# design.net
KiCad netlist of a schematic drawn in Altium Designer
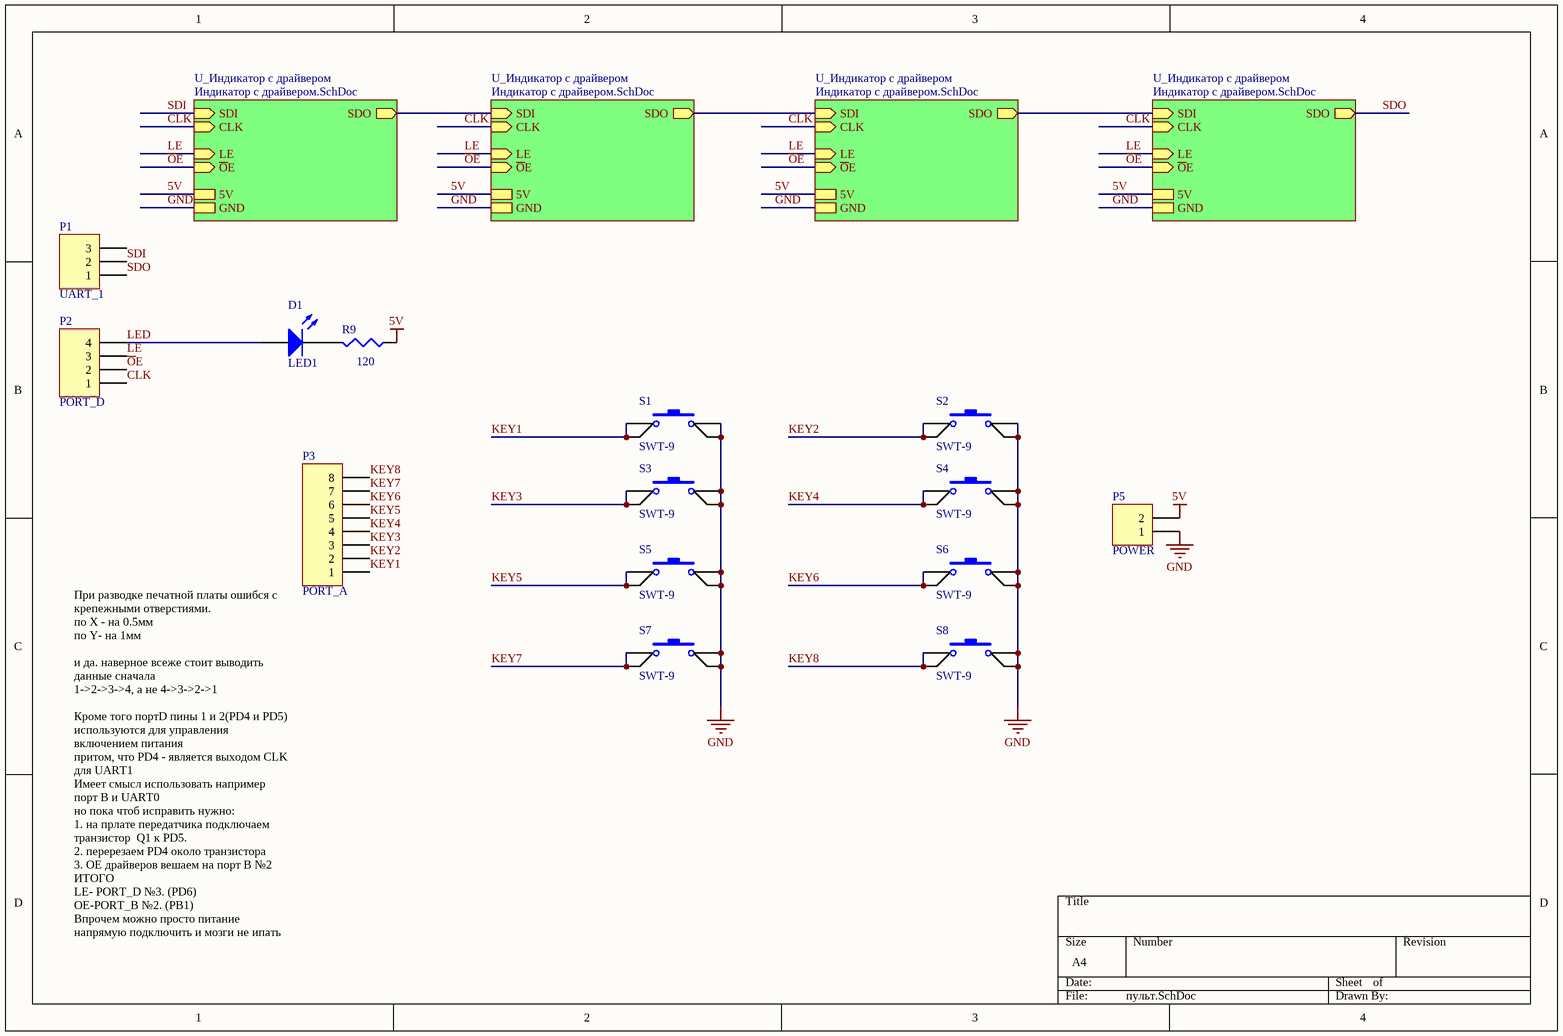
[diagram p0: пульт.SchDoc]

(export (version "E")
  (design (tool "Eeschema 10.0.6"))
  (components
    (comp (ref "D1")
      (value "LED1")
      (footprint "LED-1")
      (description "Typical RED GaAs LED")
      (fields (field (name "PUBLISHER") "Altium Limited"))
      (libsource (lib "Miscellaneous Devices") (part "LED1"))
    )
    (comp (ref "P1")
      (value "UART_1")
      (footprint "HDR1X3H")
      (description "Header, 3-Pin, Right Angle")
      (fields (field (name "PUBLISHER") "Altium Limited"))
      (libsource (lib "Miscellaneous Connectors") (part "Header 3H"))
    )
    (comp (ref "P2")
      (value "PORT_D")
      (footprint "HDR1X4H")
      (description "Header, 4-Pin, Right Angle")
      (fields (field (name "PUBLISHER") "Altium Limited"))
      (libsource (lib "Miscellaneous Connectors") (part "Header 4H"))
    )
    (comp (ref "P3")
      (value "PORT_A")
      (footprint "HDR1X8H")
      (description "Header, 8-Pin, Right Angle")
      (fields (field (name "PUBLISHER") "Altium Limited"))
      (libsource (lib "Miscellaneous Connectors") (part "Header 8H"))
    )
    (comp (ref "P5")
      (value "POWER")
      (footprint "HDR1X2H")
      (description "Header, 2-Pin, Right Angle")
      (fields (field (name "PUBLISHER") "Altium Limited"))
      (libsource (lib "Miscellaneous Connectors") (part "Header 2H"))
    )
    (comp (ref "R9")
      (value "120")
      (footprint "RESC1608L")
      (description "Resistor")
      (fields (field (name "Comment") "Res3") (field (name "PUBLISHER") "Altium Limited"))
      (libsource (lib "Miscellaneous Devices") (part "Res3"))
    )
    (comp (ref "S1")
      (value "SWT-9")
      (footprint "SWT-9")
      (description "Switch")
      (libsource (lib "LibX") (part "SWT-9"))
    )
    (comp (ref "S2")
      (value "SWT-9")
      (footprint "SWT-9")
      (description "Switch")
      (libsource (lib "LibX") (part "SWT-9"))
    )
    (comp (ref "S3")
      (value "SWT-9")
      (footprint "SWT-9")
      (description "Switch")
      (libsource (lib "LibX") (part "SWT-9"))
    )
    (comp (ref "S4")
      (value "SWT-9")
      (footprint "SWT-9")
      (description "Switch")
      (libsource (lib "LibX") (part "SWT-9"))
    )
    (comp (ref "S5")
      (value "SWT-9")
      (footprint "SWT-9")
      (description "Switch")
      (libsource (lib "LibX") (part "SWT-9"))
    )
    (comp (ref "S6")
      (value "SWT-9")
      (footprint "SWT-9")
      (description "Switch")
      (libsource (lib "LibX") (part "SWT-9"))
    )
    (comp (ref "S7")
      (value "SWT-9")
      (footprint "SWT-9")
      (description "Switch")
      (libsource (lib "LibX") (part "SWT-9"))
    )
    (comp (ref "S8")
      (value "SWT-9")
      (footprint "SWT-9")
      (description "Switch")
      (libsource (lib "LibX") (part "SWT-9"))
    )
  )
  (nets
    (net (code "1") (name "/CLK") (class "Default")
      (node (ref "P2") (pin "1") (pinfunction "1_1") (pintype "passive"))
    )
    (net (code "2") (name "/KEY1") (class "Default")
      (node (ref "P3") (pin "1") (pinfunction "1_1") (pintype "passive"))
      (node (ref "S1") (pin "1") (pinfunction "1_1") (pintype "passive"))
      (node (ref "S1") (pin "2") (pinfunction "2_2") (pintype "passive"))
    )
    (net (code "3") (name "/KEY2") (class "Default")
      (node (ref "P3") (pin "2") (pinfunction "2_2") (pintype "passive"))
      (node (ref "S2") (pin "1") (pinfunction "1_1") (pintype "passive"))
      (node (ref "S2") (pin "2") (pinfunction "2_2") (pintype "passive"))
    )
    (net (code "4") (name "/KEY3") (class "Default")
      (node (ref "P3") (pin "3") (pinfunction "3_3") (pintype "passive"))
      (node (ref "S3") (pin "1") (pinfunction "1_1") (pintype "passive"))
      (node (ref "S3") (pin "2") (pinfunction "2_2") (pintype "passive"))
    )
    (net (code "5") (name "/KEY4") (class "Default")
      (node (ref "P3") (pin "4") (pinfunction "4_4") (pintype "passive"))
      (node (ref "S4") (pin "1") (pinfunction "1_1") (pintype "passive"))
      (node (ref "S4") (pin "2") (pinfunction "2_2") (pintype "passive"))
    )
    (net (code "6") (name "/KEY5") (class "Default")
      (node (ref "P3") (pin "5") (pinfunction "5_5") (pintype "passive"))
      (node (ref "S5") (pin "1") (pinfunction "1_1") (pintype "passive"))
      (node (ref "S5") (pin "2") (pinfunction "2_2") (pintype "passive"))
    )
    (net (code "7") (name "/KEY6") (class "Default")
      (node (ref "P3") (pin "6") (pinfunction "6_6") (pintype "passive"))
      (node (ref "S6") (pin "1") (pinfunction "1_1") (pintype "passive"))
      (node (ref "S6") (pin "2") (pinfunction "2_2") (pintype "passive"))
    )
    (net (code "8") (name "/KEY7") (class "Default")
      (node (ref "P3") (pin "7") (pinfunction "7_7") (pintype "passive"))
      (node (ref "S7") (pin "1") (pinfunction "1_1") (pintype "passive"))
      (node (ref "S7") (pin "2") (pinfunction "2_2") (pintype "passive"))
    )
    (net (code "9") (name "/KEY8") (class "Default")
      (node (ref "P3") (pin "8") (pinfunction "8_8") (pintype "passive"))
      (node (ref "S8") (pin "1") (pinfunction "1_1") (pintype "passive"))
      (node (ref "S8") (pin "2") (pinfunction "2_2") (pintype "passive"))
    )
    (net (code "10") (name "/LE") (class "Default")
      (node (ref "P2") (pin "3") (pinfunction "3_3") (pintype "passive"))
    )
    (net (code "11") (name "/LED") (class "Default")
      (node (ref "D1") (pin "1") (pinfunction "A_1") (pintype "passive"))
      (node (ref "P2") (pin "4") (pinfunction "4_4") (pintype "passive"))
    )
    (net (code "12") (name "/SDI") (class "Default")
      (node (ref "P1") (pin "2") (pinfunction "2_2") (pintype "passive"))
    )
    (net (code "13") (name "/SDO") (class "Default")
      (node (ref "P1") (pin "1") (pinfunction "1_1") (pintype "passive"))
    )
    (net (code "17") (name "/~{O}E") (class "Default")
      (node (ref "P2") (pin "2") (pinfunction "2_2") (pintype "passive"))
    )
    (net (code "18") (name "5V") (class "Default")
      (node (ref "P5") (pin "2") (pinfunction "2_2") (pintype "passive"))
      (node (ref "R9") (pin "1") (pinfunction "1_1") (pintype "passive"))
    )
    (net (code "19") (name "GND") (class "Default")
      (node (ref "P5") (pin "1") (pinfunction "1_1") (pintype "passive"))
      (node (ref "S1") (pin "3") (pinfunction "3_3") (pintype "passive"))
      (node (ref "S1") (pin "4") (pinfunction "4_4") (pintype "passive"))
      (node (ref "S2") (pin "3") (pinfunction "3_3") (pintype "passive"))
      (node (ref "S2") (pin "4") (pinfunction "4_4") (pintype "passive"))
      (node (ref "S3") (pin "3") (pinfunction "3_3") (pintype "passive"))
      (node (ref "S3") (pin "4") (pinfunction "4_4") (pintype "passive"))
      (node (ref "S4") (pin "3") (pinfunction "3_3") (pintype "passive"))
      (node (ref "S4") (pin "4") (pinfunction "4_4") (pintype "passive"))
      (node (ref "S5") (pin "3") (pinfunction "3_3") (pintype "passive"))
      (node (ref "S5") (pin "4") (pinfunction "4_4") (pintype "passive"))
      (node (ref "S6") (pin "3") (pinfunction "3_3") (pintype "passive"))
      (node (ref "S6") (pin "4") (pinfunction "4_4") (pintype "passive"))
      (node (ref "S7") (pin "3") (pinfunction "3_3") (pintype "passive"))
      (node (ref "S7") (pin "4") (pinfunction "4_4") (pintype "passive"))
      (node (ref "S8") (pin "3") (pinfunction "3_3") (pintype "passive"))
      (node (ref "S8") (pin "4") (pinfunction "4_4") (pintype "passive"))
    )
    (net (code "20") (name "Net-(D1-K)") (class "Default")
      (node (ref "D1") (pin "2") (pinfunction "K_2") (pintype "passive"))
      (node (ref "R9") (pin "2") (pinfunction "2_2") (pintype "passive"))
    )
    (net (code "21") (name "unconnected-(P1-Pad3)") (class "Default")
      (node (ref "P1") (pin "3") (pinfunction "3_3") (pintype "passive"))
    )
  )
)
